# ProProject_8__2024-05-28.net
KiCad netlist of a schematic drawn in EasyEDA Pro
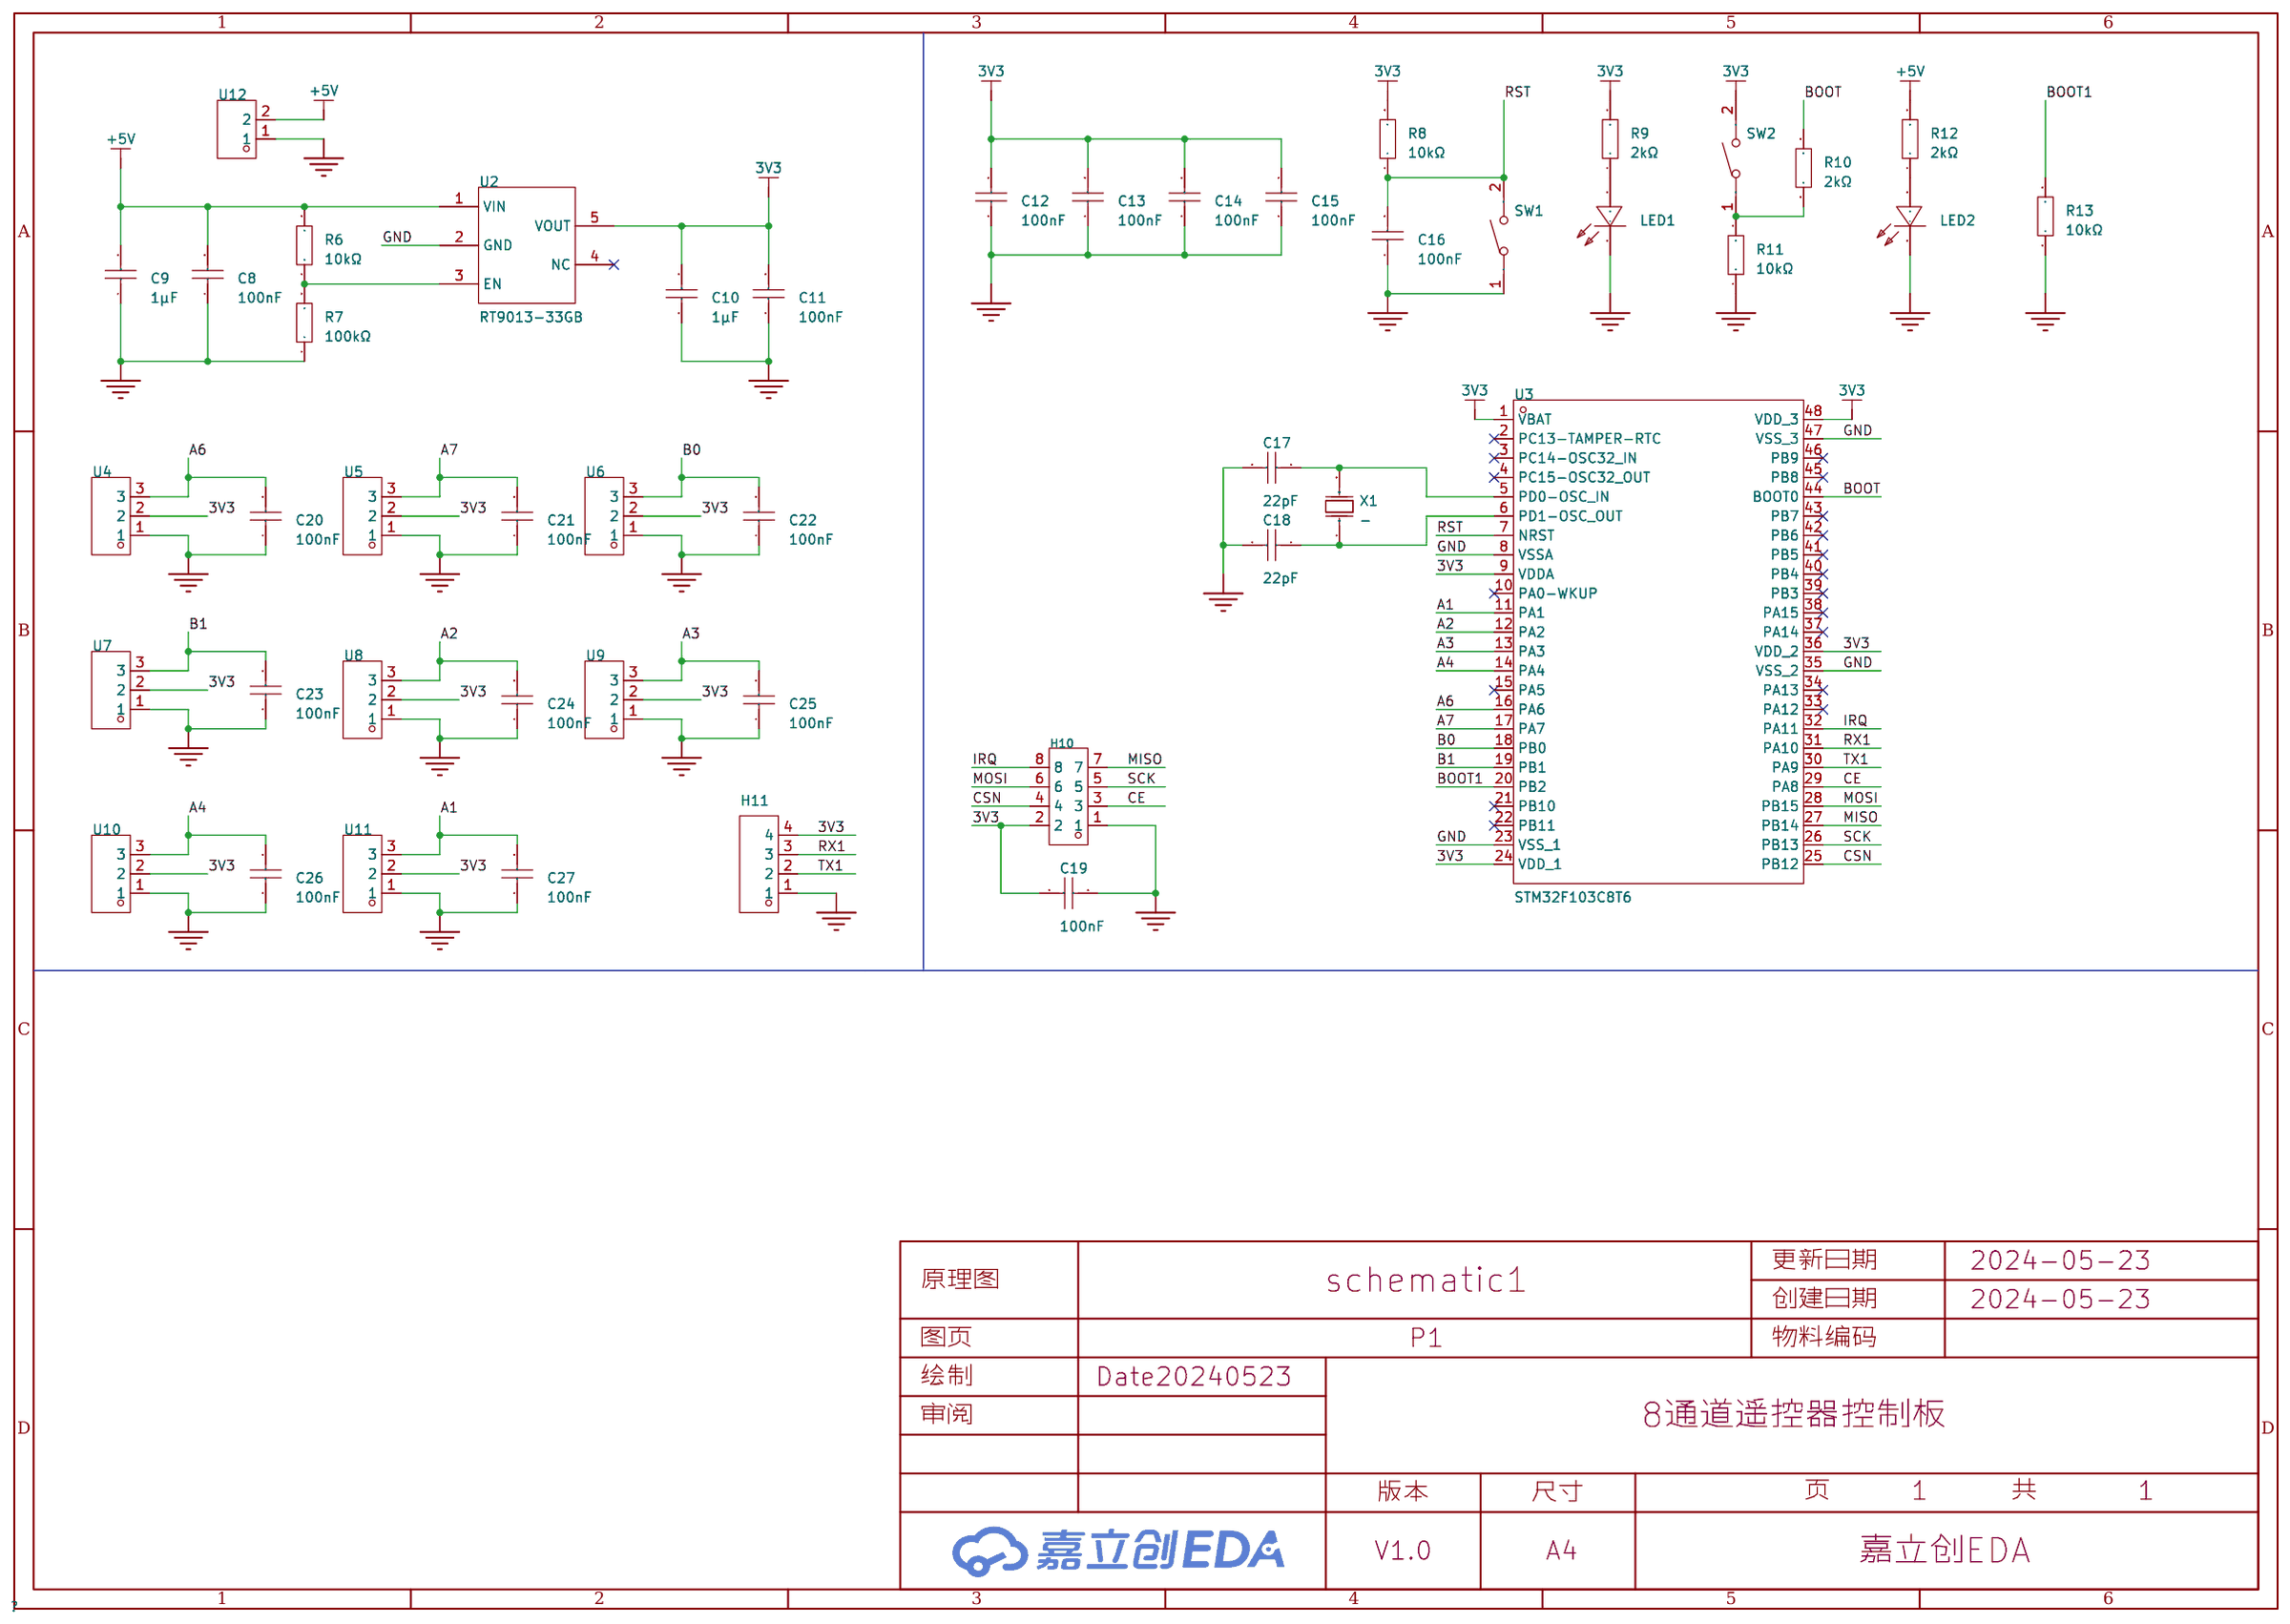
[diagram p0: schematic sheet]

(export (version "E")
  (design (tool "Eeschema 10.0.6"))
  (components
    (comp (ref "C8")
      (value "100nF")
      (footprint "easyedapro:C0805")
      (description "容值:100nF;精度:±10%;额定电压:50V;材质(温度系数):X7R;")
      (fields
        (field (name "Manufacturer Part") "CC0805KRX7R9BB104")
        (field (name "Manufacturer") "YAGEO(国巨)")
      )
      (libsource (lib "easyedapro") (part "CC0805KRX7R9BB104"))
    )
    (comp (ref "C9")
      (value "1μF")
      (footprint "easyedapro:C0805")
      (description "容值:100nF;精度:±10%;额定电压:50V;材质(温度系数):X7R;")
      (fields
        (field (name "Manufacturer Part") "CC0805KRX7R9BB104")
        (field (name "Manufacturer") "YAGEO(国巨)")
      )
      (libsource (lib "easyedapro") (part "CC0805KRX7R9BB104"))
    )
    (comp (ref "C10")
      (value "1μF")
      (footprint "easyedapro:C0805")
      (description "容值:100nF;精度:±10%;额定电压:50V;材质(温度系数):X7R;")
      (fields
        (field (name "Manufacturer Part") "CC0805KRX7R9BB104")
        (field (name "Manufacturer") "YAGEO(国巨)")
      )
      (libsource (lib "easyedapro") (part "CC0805KRX7R9BB104"))
    )
    (comp (ref "C11")
      (value "100nF")
      (footprint "easyedapro:C0805")
      (description "容值:100nF;精度:±10%;额定电压:50V;材质(温度系数):X7R;")
      (fields
        (field (name "Manufacturer Part") "CC0805KRX7R9BB104")
        (field (name "Manufacturer") "YAGEO(国巨)")
      )
      (libsource (lib "easyedapro") (part "CC0805KRX7R9BB104"))
    )
    (comp (ref "C12")
      (value "100nF")
      (footprint "easyedapro:C0805")
      (description "容值:100nF;精度:±10%;额定电压:50V;材质(温度系数):X7R;")
      (fields
        (field (name "Manufacturer Part") "CC0805KRX7R9BB104")
        (field (name "Manufacturer") "YAGEO(国巨)")
      )
      (libsource (lib "easyedapro") (part "CC0805KRX7R9BB104"))
    )
    (comp (ref "C13")
      (value "100nF")
      (footprint "easyedapro:C0805")
      (description "容值:100nF;精度:±10%;额定电压:50V;材质(温度系数):X7R;")
      (fields
        (field (name "Manufacturer Part") "CC0805KRX7R9BB104")
        (field (name "Manufacturer") "YAGEO(国巨)")
      )
      (libsource (lib "easyedapro") (part "CC0805KRX7R9BB104"))
    )
    (comp (ref "C14")
      (value "100nF")
      (footprint "easyedapro:C0805")
      (description "容值:100nF;精度:±10%;额定电压:50V;材质(温度系数):X7R;")
      (fields
        (field (name "Manufacturer Part") "CC0805KRX7R9BB104")
        (field (name "Manufacturer") "YAGEO(国巨)")
      )
      (libsource (lib "easyedapro") (part "CC0805KRX7R9BB104"))
    )
    (comp (ref "C15")
      (value "100nF")
      (footprint "easyedapro:C0805")
      (description "容值:100nF;精度:±10%;额定电压:50V;材质(温度系数):X7R;")
      (fields
        (field (name "Manufacturer Part") "CC0805KRX7R9BB104")
        (field (name "Manufacturer") "YAGEO(国巨)")
      )
      (libsource (lib "easyedapro") (part "CC0805KRX7R9BB104"))
    )
    (comp (ref "C16")
      (value "100nF")
      (footprint "easyedapro:C0805")
      (description "容值:100nF;精度:±10%;额定电压:50V;材质(温度系数):X7R;")
      (fields
        (field (name "Manufacturer Part") "CC0805KRX7R9BB104")
        (field (name "Manufacturer") "YAGEO(国巨)")
      )
      (libsource (lib "easyedapro") (part "CC0805KRX7R9BB104"))
    )
    (comp (ref "C17")
      (value "22pF")
      (footprint "easyedapro:C0805")
      (description "容值:100nF;精度:±10%;额定电压:50V;材质(温度系数):X7R;")
      (fields
        (field (name "Manufacturer Part") "CC0805KRX7R9BB104")
        (field (name "Manufacturer") "YAGEO(国巨)")
      )
      (libsource (lib "easyedapro") (part "CC0805KRX7R9BB104"))
    )
    (comp (ref "C18")
      (value "22pF")
      (footprint "easyedapro:C0805")
      (description "容值:100nF;精度:±10%;额定电压:50V;材质(温度系数):X7R;")
      (fields
        (field (name "Manufacturer Part") "CC0805KRX7R9BB104")
        (field (name "Manufacturer") "YAGEO(国巨)")
      )
      (libsource (lib "easyedapro") (part "CC0805KRX7R9BB104"))
    )
    (comp (ref "C19")
      (value "100nF")
      (footprint "easyedapro:C0805")
      (description "容值:100nF;精度:±10%;额定电压:50V;材质(温度系数):X7R;")
      (fields
        (field (name "Manufacturer Part") "CC0805KRX7R9BB104")
        (field (name "Manufacturer") "YAGEO(国巨)")
      )
      (libsource (lib "easyedapro") (part "CC0805KRX7R9BB104"))
    )
    (comp (ref "C20")
      (value "100nF")
      (footprint "easyedapro:C0805")
      (description "容值:100nF;精度:±10%;额定电压:50V;材质(温度系数):X7R;")
      (fields
        (field (name "Manufacturer Part") "CC0805KRX7R9BB104")
        (field (name "Manufacturer") "YAGEO(国巨)")
      )
      (libsource (lib "easyedapro") (part "CC0805KRX7R9BB104"))
    )
    (comp (ref "C21")
      (value "100nF")
      (footprint "easyedapro:C0805")
      (description "容值:100nF;精度:±10%;额定电压:50V;材质(温度系数):X7R;")
      (fields
        (field (name "Manufacturer Part") "CC0805KRX7R9BB104")
        (field (name "Manufacturer") "YAGEO(国巨)")
      )
      (libsource (lib "easyedapro") (part "CC0805KRX7R9BB104"))
    )
    (comp (ref "C22")
      (value "100nF")
      (footprint "easyedapro:C0805")
      (description "容值:100nF;精度:±10%;额定电压:50V;材质(温度系数):X7R;")
      (fields
        (field (name "Manufacturer Part") "CC0805KRX7R9BB104")
        (field (name "Manufacturer") "YAGEO(国巨)")
      )
      (libsource (lib "easyedapro") (part "CC0805KRX7R9BB104"))
    )
    (comp (ref "C23")
      (value "100nF")
      (footprint "easyedapro:C0805")
      (description "容值:100nF;精度:±10%;额定电压:50V;材质(温度系数):X7R;")
      (fields
        (field (name "Manufacturer Part") "CC0805KRX7R9BB104")
        (field (name "Manufacturer") "YAGEO(国巨)")
      )
      (libsource (lib "easyedapro") (part "CC0805KRX7R9BB104"))
    )
    (comp (ref "C24")
      (value "100nF")
      (footprint "easyedapro:C0805")
      (description "容值:100nF;精度:±10%;额定电压:50V;材质(温度系数):X7R;")
      (fields
        (field (name "Manufacturer Part") "CC0805KRX7R9BB104")
        (field (name "Manufacturer") "YAGEO(国巨)")
      )
      (libsource (lib "easyedapro") (part "CC0805KRX7R9BB104"))
    )
    (comp (ref "C25")
      (value "100nF")
      (footprint "easyedapro:C0805")
      (description "容值:100nF;精度:±10%;额定电压:50V;材质(温度系数):X7R;")
      (fields
        (field (name "Manufacturer Part") "CC0805KRX7R9BB104")
        (field (name "Manufacturer") "YAGEO(国巨)")
      )
      (libsource (lib "easyedapro") (part "CC0805KRX7R9BB104"))
    )
    (comp (ref "C26")
      (value "100nF")
      (footprint "easyedapro:C0805")
      (description "容值:100nF;精度:±10%;额定电压:50V;材质(温度系数):X7R;")
      (fields
        (field (name "Manufacturer Part") "CC0805KRX7R9BB104")
        (field (name "Manufacturer") "YAGEO(国巨)")
      )
      (libsource (lib "easyedapro") (part "CC0805KRX7R9BB104"))
    )
    (comp (ref "C27")
      (value "100nF")
      (footprint "easyedapro:C0805")
      (description "容值:100nF;精度:±10%;额定电压:50V;材质(温度系数):X7R;")
      (fields
        (field (name "Manufacturer Part") "CC0805KRX7R9BB104")
        (field (name "Manufacturer") "YAGEO(国巨)")
      )
      (libsource (lib "easyedapro") (part "CC0805KRX7R9BB104"))
    )
    (comp (ref "H10")
      (value "PZ254V-12-8P")
      (footprint "easyedapro:HDR-TH_8P-P2.54-V-M-R2-C4-S2.54")
      (fields (field (name "Manufacturer") "XFCN(兴飞)"))
      (libsource (lib "easyedapro") (part "PZ254V-12-8P"))
    )
    (comp (ref "H11")
      (value "PZ254V-11-04P")
      (footprint "easyedapro:HDR-TH_4P-P2.54-V-M")
      (fields (field (name "Manufacturer") "XFCN(兴飞)"))
      (libsource (lib "easyedapro") (part "PZ254V-11-04P_C2691448"))
    )
    (comp (ref "LED1")
      (value "SZYY0603G")
      (footprint "easyedapro:LED0603-R-RD_GREEN")
      (description "发光颜色:翠绿色;")
      (fields (field (name "Manufacturer") "yongyu(永裕光电)"))
      (libsource (lib "easyedapro") (part "SZYY0603G"))
    )
    (comp (ref "LED2")
      (value "SZYY0603G")
      (footprint "easyedapro:LED0603-R-RD_GREEN")
      (description "发光颜色:翠绿色;")
      (fields (field (name "Manufacturer") "yongyu(永裕光电)"))
      (libsource (lib "easyedapro") (part "SZYY0603G"))
    )
    (comp (ref "R6")
      (value "10kΩ")
      (footprint "easyedapro:R0603")
      (description "电阻类型:厚膜电阻;阻值:1kΩ;精度:±1%;功率:100mW;最大工作电压:75V;温度系数:±100ppm/°C;")
      (fields
        (field (name "Manufacturer Part") "0603WAF1001T5E")
        (field (name "Manufacturer") "UNI-ROYAL(厚声)")
      )
      (libsource (lib "easyedapro") (part "0603WAF1001T5E"))
    )
    (comp (ref "R7")
      (value "100kΩ")
      (footprint "easyedapro:R0603")
      (description "电阻类型:厚膜电阻;阻值:1kΩ;精度:±1%;功率:100mW;最大工作电压:75V;温度系数:±100ppm/°C;")
      (fields
        (field (name "Manufacturer Part") "0603WAF1001T5E")
        (field (name "Manufacturer") "UNI-ROYAL(厚声)")
      )
      (libsource (lib "easyedapro") (part "0603WAF1001T5E"))
    )
    (comp (ref "R8")
      (value "10kΩ")
      (footprint "easyedapro:R0603")
      (description "电阻类型:厚膜电阻;阻值:1kΩ;精度:±1%;功率:100mW;最大工作电压:75V;温度系数:±100ppm/°C;")
      (fields
        (field (name "Manufacturer Part") "0603WAF1001T5E")
        (field (name "Manufacturer") "UNI-ROYAL(厚声)")
      )
      (libsource (lib "easyedapro") (part "0603WAF1001T5E"))
    )
    (comp (ref "R9")
      (value "2kΩ")
      (footprint "easyedapro:R0603")
      (description "电阻类型:厚膜电阻;阻值:1kΩ;精度:±1%;功率:100mW;最大工作电压:75V;温度系数:±100ppm/°C;")
      (fields
        (field (name "Manufacturer Part") "0603WAF1001T5E")
        (field (name "Manufacturer") "UNI-ROYAL(厚声)")
      )
      (libsource (lib "easyedapro") (part "0603WAF1001T5E"))
    )
    (comp (ref "R10")
      (value "2kΩ")
      (footprint "easyedapro:R0603")
      (description "电阻类型:厚膜电阻;阻值:1kΩ;精度:±1%;功率:100mW;最大工作电压:75V;温度系数:±100ppm/°C;")
      (fields
        (field (name "Manufacturer Part") "0603WAF1001T5E")
        (field (name "Manufacturer") "UNI-ROYAL(厚声)")
      )
      (libsource (lib "easyedapro") (part "0603WAF1001T5E"))
    )
    (comp (ref "R11")
      (value "10kΩ")
      (footprint "easyedapro:R0603")
      (description "电阻类型:厚膜电阻;阻值:1kΩ;精度:±1%;功率:100mW;最大工作电压:75V;温度系数:±100ppm/°C;")
      (fields
        (field (name "Manufacturer Part") "0603WAF1001T5E")
        (field (name "Manufacturer") "UNI-ROYAL(厚声)")
      )
      (libsource (lib "easyedapro") (part "0603WAF1001T5E"))
    )
    (comp (ref "R12")
      (value "2kΩ")
      (footprint "easyedapro:R0603")
      (description "电阻类型:厚膜电阻;阻值:1kΩ;精度:±1%;功率:100mW;最大工作电压:75V;温度系数:±100ppm/°C;")
      (fields
        (field (name "Manufacturer Part") "0603WAF1001T5E")
        (field (name "Manufacturer") "UNI-ROYAL(厚声)")
      )
      (libsource (lib "easyedapro") (part "0603WAF1001T5E"))
    )
    (comp (ref "R13")
      (value "10kΩ")
      (footprint "easyedapro:R0603")
      (description "电阻类型:厚膜电阻;阻值:1kΩ;精度:±1%;功率:100mW;最大工作电压:75V;温度系数:±100ppm/°C;")
      (fields
        (field (name "Manufacturer Part") "0603WAF1001T5E")
        (field (name "Manufacturer") "UNI-ROYAL(厚声)")
      )
      (libsource (lib "easyedapro") (part "0603WAF1001T5E"))
    )
    (comp (ref "SW1")
      (value "TS-1088-AR02016")
      (footprint "easyedapro:SW-SMD_L3.9-W3.0-P4.45")
      (fields (field (name "Manufacturer") "XUNPU(讯普)"))
      (libsource (lib "easyedapro") (part "TS-1088-AR02016"))
    )
    (comp (ref "SW2")
      (value "TS-1088-AR02016")
      (footprint "easyedapro:SW-SMD_L3.9-W3.0-P4.45")
      (fields (field (name "Manufacturer") "XUNPU(讯普)"))
      (libsource (lib "easyedapro") (part "TS-1088-AR02016"))
    )
    (comp (ref "U2")
      (value "RT9013-33GB")
      (footprint "easyedapro:SOT-23-5_L3.0-W1.7-P0.95-LS2.8-BL")
      (description "输出类型:固定;最大输入电压:5.5V;输出电压:3.3V;最大输出电流:500mA;电源纹波抑制比(PSRR):50dB@(10kHz);输出极性:正极;")
      (fields (field (name "Manufacturer") "RICHTEK(立锜)"))
      (libsource (lib "easyedapro") (part "RT9013-33GB"))
    )
    (comp (ref "U3")
      (value "STM32F103C8T6")
      (footprint "easyedapro:LQFP-48_L7.0-W7.0-P0.50-LS9.0-BL")
      (description "CPU内核:CM3;程序存储容量:64KB;RAM总容量:20KB;GPIO端口数量:37;工作电压范围:2V~3.6V;CPU最大主频:72MHz;程序存储器类型:FLASH;")
      (fields (field (name "Manufacturer") "ST(意法半导体)"))
      (libsource (lib "easyedapro") (part "STM32F103C8T6"))
    )
    (comp (ref "U4")
      (value "ZX-XH2.54-3PZZ")
      (footprint "easyedapro:CONN-TH_3P-P2.54_2501S-3P")
      (fields (field (name "Manufacturer") "Megastar(兆星)"))
      (libsource (lib "easyedapro") (part "ZX-XH2.54-3PZZ"))
    )
    (comp (ref "U5")
      (value "ZX-XH2.54-3PZZ")
      (footprint "easyedapro:CONN-TH_3P-P2.54_2501S-3P")
      (fields (field (name "Manufacturer") "Megastar(兆星)"))
      (libsource (lib "easyedapro") (part "ZX-XH2.54-3PZZ"))
    )
    (comp (ref "U6")
      (value "ZX-XH2.54-3PZZ")
      (footprint "easyedapro:CONN-TH_3P-P2.54_2501S-3P")
      (fields (field (name "Manufacturer") "Megastar(兆星)"))
      (libsource (lib "easyedapro") (part "ZX-XH2.54-3PZZ"))
    )
    (comp (ref "U7")
      (value "ZX-XH2.54-3PZZ")
      (footprint "easyedapro:CONN-TH_3P-P2.54_2501S-3P")
      (fields (field (name "Manufacturer") "Megastar(兆星)"))
      (libsource (lib "easyedapro") (part "ZX-XH2.54-3PZZ"))
    )
    (comp (ref "U8")
      (value "ZX-XH2.54-3PZZ")
      (footprint "easyedapro:CONN-TH_3P-P2.54_2501S-3P")
      (fields (field (name "Manufacturer") "Megastar(兆星)"))
      (libsource (lib "easyedapro") (part "ZX-XH2.54-3PZZ"))
    )
    (comp (ref "U9")
      (value "ZX-XH2.54-3PZZ")
      (footprint "easyedapro:CONN-TH_3P-P2.54_2501S-3P")
      (fields (field (name "Manufacturer") "Megastar(兆星)"))
      (libsource (lib "easyedapro") (part "ZX-XH2.54-3PZZ"))
    )
    (comp (ref "U10")
      (value "ZX-XH2.54-3PZZ")
      (footprint "easyedapro:CONN-TH_3P-P2.54_2501S-3P")
      (fields (field (name "Manufacturer") "Megastar(兆星)"))
      (libsource (lib "easyedapro") (part "ZX-XH2.54-3PZZ"))
    )
    (comp (ref "U11")
      (value "ZX-XH2.54-3PZZ")
      (footprint "easyedapro:CONN-TH_3P-P2.54_2501S-3P")
      (fields (field (name "Manufacturer") "Megastar(兆星)"))
      (libsource (lib "easyedapro") (part "ZX-XH2.54-3PZZ"))
    )
    (comp (ref "U12")
      (value "DB125-3.81-2P-GN-S")
      (footprint "easyedapro:CONN-TH_2P-P3.81_L7.4-W7.6")
      (fields (field (name "Manufacturer") "DORABO(地博电气)"))
      (libsource (lib "easyedapro") (part "DB125-3.81-2P"))
    )
    (comp (ref "X1")
      (value "-")
      (footprint "easyedapro:HC-49S_L11.4-W4.8")
      (description "晶振类型:-;频率:-;外接负载电容:-;")
      (fields (field (name "Manufacturer Part") "9C08000003") (field (name "Manufacturer") "TXC(晶技)"))
      (libsource (lib "easyedapro") (part "9C0803LCSC-DDK2S"))
    )
  )
  (nets
    (net (code "1") (name "+5V") (class "Default")
      (node (ref "C8") (pin "2") (pinfunction "2_2") (pintype "input"))
      (node (ref "C9") (pin "2") (pinfunction "2_2") (pintype "input"))
      (node (ref "R12") (pin "2") (pinfunction "2_2") (pintype "input"))
      (node (ref "R6") (pin "2") (pinfunction "2_2") (pintype "input"))
      (node (ref "U12") (pin "2") (pinfunction "2_2") (pintype "unspecified"))
      (node (ref "U2") (pin "1") (pinfunction "VIN_1") (pintype "unspecified"))
    )
    (net (code "2") (name "/A1") (class "Default")
      (node (ref "C27") (pin "2") (pinfunction "2_2") (pintype "input"))
      (node (ref "U11") (pin "3") (pinfunction "3_3") (pintype "unspecified"))
      (node (ref "U3") (pin "11") (pinfunction "PA1_11") (pintype "unspecified"))
    )
    (net (code "3") (name "/A2") (class "Default")
      (node (ref "C24") (pin "2") (pinfunction "2_2") (pintype "input"))
      (node (ref "U3") (pin "12") (pinfunction "PA2_12") (pintype "unspecified"))
      (node (ref "U8") (pin "3") (pinfunction "3_3") (pintype "unspecified"))
    )
    (net (code "4") (name "/A3") (class "Default")
      (node (ref "C25") (pin "2") (pinfunction "2_2") (pintype "input"))
      (node (ref "U3") (pin "13") (pinfunction "PA3_13") (pintype "unspecified"))
      (node (ref "U9") (pin "3") (pinfunction "3_3") (pintype "unspecified"))
    )
    (net (code "5") (name "/A4") (class "Default")
      (node (ref "C26") (pin "2") (pinfunction "2_2") (pintype "input"))
      (node (ref "U10") (pin "3") (pinfunction "3_3") (pintype "unspecified"))
      (node (ref "U3") (pin "14") (pinfunction "PA4_14") (pintype "unspecified"))
    )
    (net (code "6") (name "/A6") (class "Default")
      (node (ref "C20") (pin "2") (pinfunction "2_2") (pintype "input"))
      (node (ref "U3") (pin "16") (pinfunction "PA6_16") (pintype "unspecified"))
      (node (ref "U4") (pin "3") (pinfunction "3_3") (pintype "unspecified"))
    )
    (net (code "7") (name "/A7") (class "Default")
      (node (ref "C21") (pin "2") (pinfunction "2_2") (pintype "input"))
      (node (ref "U3") (pin "17") (pinfunction "PA7_17") (pintype "unspecified"))
      (node (ref "U5") (pin "3") (pinfunction "3_3") (pintype "unspecified"))
    )
    (net (code "8") (name "/B0") (class "Default")
      (node (ref "C22") (pin "2") (pinfunction "2_2") (pintype "input"))
      (node (ref "U3") (pin "18") (pinfunction "PB0_18") (pintype "unspecified"))
      (node (ref "U6") (pin "3") (pinfunction "3_3") (pintype "unspecified"))
    )
    (net (code "9") (name "/B1") (class "Default")
      (node (ref "C23") (pin "2") (pinfunction "2_2") (pintype "input"))
      (node (ref "U3") (pin "19") (pinfunction "PB1_19") (pintype "unspecified"))
      (node (ref "U7") (pin "3") (pinfunction "3_3") (pintype "unspecified"))
    )
    (net (code "10") (name "/BOOT") (class "Default")
      (node (ref "R10") (pin "2") (pinfunction "2_2") (pintype "input"))
      (node (ref "U3") (pin "44") (pinfunction "BOOT0_44") (pintype "unspecified"))
    )
    (net (code "11") (name "/BOOT1") (class "Default")
      (node (ref "R13") (pin "2") (pinfunction "2_2") (pintype "input"))
      (node (ref "U3") (pin "20") (pinfunction "PB2_20") (pintype "unspecified"))
    )
    (net (code "12") (name "/CE") (class "Default")
      (node (ref "H10") (pin "3") (pinfunction "3_3") (pintype "input"))
      (node (ref "U3") (pin "29") (pinfunction "PA8_29") (pintype "unspecified"))
    )
    (net (code "13") (name "/CSN") (class "Default")
      (node (ref "H10") (pin "4") (pinfunction "4_4") (pintype "input"))
      (node (ref "U3") (pin "25") (pinfunction "PB12_25") (pintype "unspecified"))
    )
    (net (code "14") (name "/IRQ") (class "Default")
      (node (ref "H10") (pin "8") (pinfunction "8_8") (pintype "input"))
      (node (ref "U3") (pin "32") (pinfunction "PA11_32") (pintype "unspecified"))
    )
    (net (code "15") (name "/MISO") (class "Default")
      (node (ref "H10") (pin "7") (pinfunction "7_7") (pintype "input"))
      (node (ref "U3") (pin "27") (pinfunction "PB14_27") (pintype "unspecified"))
    )
    (net (code "16") (name "/MOSI") (class "Default")
      (node (ref "H10") (pin "6") (pinfunction "6_6") (pintype "input"))
      (node (ref "U3") (pin "28") (pinfunction "PB15_28") (pintype "unspecified"))
    )
    (net (code "17") (name "/RST") (class "Default")
      (node (ref "C16") (pin "2") (pinfunction "2_2") (pintype "input"))
      (node (ref "R8") (pin "1") (pinfunction "1_1") (pintype "input"))
      (node (ref "SW1") (pin "2") (pinfunction "2_2") (pintype "unspecified"))
      (node (ref "U3") (pin "7") (pinfunction "NRST_7") (pintype "unspecified"))
    )
    (net (code "18") (name "/RX1") (class "Default")
      (node (ref "H11") (pin "3") (pinfunction "3_3") (pintype "unspecified"))
      (node (ref "U3") (pin "31") (pinfunction "PA10_31") (pintype "unspecified"))
    )
    (net (code "19") (name "/SCK") (class "Default")
      (node (ref "H10") (pin "5") (pinfunction "5_5") (pintype "input"))
      (node (ref "U3") (pin "26") (pinfunction "PB13_26") (pintype "unspecified"))
    )
    (net (code "20") (name "/TX1") (class "Default")
      (node (ref "H11") (pin "2") (pinfunction "2_2") (pintype "unspecified"))
      (node (ref "U3") (pin "30") (pinfunction "PA9_30") (pintype "unspecified"))
    )
    (net (code "21") (name "3V3") (class "Default")
      (node (ref "C10") (pin "2") (pinfunction "2_2") (pintype "input"))
      (node (ref "C11") (pin "2") (pinfunction "2_2") (pintype "input"))
      (node (ref "C12") (pin "2") (pinfunction "2_2") (pintype "input"))
      (node (ref "C13") (pin "2") (pinfunction "2_2") (pintype "input"))
      (node (ref "C14") (pin "2") (pinfunction "2_2") (pintype "input"))
      (node (ref "C15") (pin "2") (pinfunction "2_2") (pintype "input"))
      (node (ref "C19") (pin "1") (pinfunction "1_1") (pintype "input"))
      (node (ref "H10") (pin "2") (pinfunction "2_2") (pintype "input"))
      (node (ref "H11") (pin "4") (pinfunction "4_4") (pintype "unspecified"))
      (node (ref "R8") (pin "2") (pinfunction "2_2") (pintype "input"))
      (node (ref "R9") (pin "2") (pinfunction "2_2") (pintype "input"))
      (node (ref "SW2") (pin "2") (pinfunction "2_2") (pintype "unspecified"))
      (node (ref "U10") (pin "2") (pinfunction "2_2") (pintype "unspecified"))
      (node (ref "U11") (pin "2") (pinfunction "2_2") (pintype "unspecified"))
      (node (ref "U2") (pin "5") (pinfunction "VOUT_5") (pintype "unspecified"))
      (node (ref "U3") (pin "1") (pinfunction "VBAT_1") (pintype "unspecified"))
      (node (ref "U3") (pin "24") (pinfunction "VDD_1_24") (pintype "unspecified"))
      (node (ref "U3") (pin "36") (pinfunction "VDD_2_36") (pintype "unspecified"))
      (node (ref "U3") (pin "48") (pinfunction "VDD_3_48") (pintype "unspecified"))
      (node (ref "U3") (pin "9") (pinfunction "VDDA_9") (pintype "unspecified"))
      (node (ref "U4") (pin "2") (pinfunction "2_2") (pintype "unspecified"))
      (node (ref "U5") (pin "2") (pinfunction "2_2") (pintype "unspecified"))
      (node (ref "U6") (pin "2") (pinfunction "2_2") (pintype "unspecified"))
      (node (ref "U7") (pin "2") (pinfunction "2_2") (pintype "unspecified"))
      (node (ref "U8") (pin "2") (pinfunction "2_2") (pintype "unspecified"))
      (node (ref "U9") (pin "2") (pinfunction "2_2") (pintype "unspecified"))
    )
    (net (code "22") (name "GND") (class "Default")
      (node (ref "C10") (pin "1") (pinfunction "1_1") (pintype "input"))
      (node (ref "C11") (pin "1") (pinfunction "1_1") (pintype "input"))
      (node (ref "C12") (pin "1") (pinfunction "1_1") (pintype "input"))
      (node (ref "C13") (pin "1") (pinfunction "1_1") (pintype "input"))
      (node (ref "C14") (pin "1") (pinfunction "1_1") (pintype "input"))
      (node (ref "C15") (pin "1") (pinfunction "1_1") (pintype "input"))
      (node (ref "C16") (pin "1") (pinfunction "1_1") (pintype "input"))
      (node (ref "C17") (pin "2") (pinfunction "2_2") (pintype "input"))
      (node (ref "C18") (pin "2") (pinfunction "2_2") (pintype "input"))
      (node (ref "C19") (pin "2") (pinfunction "2_2") (pintype "input"))
      (node (ref "C20") (pin "1") (pinfunction "1_1") (pintype "input"))
      (node (ref "C21") (pin "1") (pinfunction "1_1") (pintype "input"))
      (node (ref "C22") (pin "1") (pinfunction "1_1") (pintype "input"))
      (node (ref "C23") (pin "1") (pinfunction "1_1") (pintype "input"))
      (node (ref "C24") (pin "1") (pinfunction "1_1") (pintype "input"))
      (node (ref "C25") (pin "1") (pinfunction "1_1") (pintype "input"))
      (node (ref "C26") (pin "1") (pinfunction "1_1") (pintype "input"))
      (node (ref "C27") (pin "1") (pinfunction "1_1") (pintype "input"))
      (node (ref "C8") (pin "1") (pinfunction "1_1") (pintype "input"))
      (node (ref "C9") (pin "1") (pinfunction "1_1") (pintype "input"))
      (node (ref "H10") (pin "1") (pinfunction "1_1") (pintype "input"))
      (node (ref "H11") (pin "1") (pinfunction "1_1") (pintype "unspecified"))
      (node (ref "LED1") (pin "2") (pinfunction "-_2") (pintype "unspecified"))
      (node (ref "LED2") (pin "2") (pinfunction "-_2") (pintype "unspecified"))
      (node (ref "R11") (pin "1") (pinfunction "1_1") (pintype "input"))
      (node (ref "R13") (pin "1") (pinfunction "1_1") (pintype "input"))
      (node (ref "R7") (pin "1") (pinfunction "1_1") (pintype "input"))
      (node (ref "SW1") (pin "1") (pinfunction "1_1") (pintype "unspecified"))
      (node (ref "U10") (pin "1") (pinfunction "1_1") (pintype "unspecified"))
      (node (ref "U11") (pin "1") (pinfunction "1_1") (pintype "unspecified"))
      (node (ref "U12") (pin "1") (pinfunction "1_1") (pintype "unspecified"))
      (node (ref "U2") (pin "2") (pinfunction "GND_2") (pintype "unspecified"))
      (node (ref "U3") (pin "23") (pinfunction "VSS_1_23") (pintype "unspecified"))
      (node (ref "U3") (pin "35") (pinfunction "VSS_2_35") (pintype "unspecified"))
      (node (ref "U3") (pin "47") (pinfunction "VSS_3_47") (pintype "unspecified"))
      (node (ref "U3") (pin "8") (pinfunction "VSSA_8") (pintype "unspecified"))
      (node (ref "U4") (pin "1") (pinfunction "1_1") (pintype "unspecified"))
      (node (ref "U5") (pin "1") (pinfunction "1_1") (pintype "unspecified"))
      (node (ref "U6") (pin "1") (pinfunction "1_1") (pintype "unspecified"))
      (node (ref "U7") (pin "1") (pinfunction "1_1") (pintype "unspecified"))
      (node (ref "U8") (pin "1") (pinfunction "1_1") (pintype "unspecified"))
      (node (ref "U9") (pin "1") (pinfunction "1_1") (pintype "unspecified"))
    )
    (net (code "23") (name "Net-(LED1-+)") (class "Default")
      (node (ref "LED1") (pin "1") (pinfunction "+_1") (pintype "unspecified"))
      (node (ref "R9") (pin "1") (pinfunction "1_1") (pintype "input"))
    )
    (net (code "24") (name "Net-(LED2-+)") (class "Default")
      (node (ref "LED2") (pin "1") (pinfunction "+_1") (pintype "unspecified"))
      (node (ref "R12") (pin "1") (pinfunction "1_1") (pintype "input"))
    )
    (net (code "25") (name "Net-(R10-Pad1)") (class "Default")
      (node (ref "R10") (pin "1") (pinfunction "1_1") (pintype "input"))
      (node (ref "R11") (pin "2") (pinfunction "2_2") (pintype "input"))
      (node (ref "SW2") (pin "1") (pinfunction "1_1") (pintype "unspecified"))
    )
    (net (code "26") (name "Net-(U2-EN)") (class "Default")
      (node (ref "R6") (pin "1") (pinfunction "1_1") (pintype "input"))
      (node (ref "R7") (pin "2") (pinfunction "2_2") (pintype "input"))
      (node (ref "U2") (pin "3") (pinfunction "EN_3") (pintype "unspecified"))
    )
    (net (code "27") (name "Net-(U3-PD0-OSC_IN)") (class "Default")
      (node (ref "C17") (pin "1") (pinfunction "1_1") (pintype "input"))
      (node (ref "U3") (pin "5") (pinfunction "PD0-OSC_IN_5") (pintype "unspecified"))
      (node (ref "X1") (pin "2") (pinfunction "OSC2_2") (pintype "input"))
    )
    (net (code "28") (name "Net-(U3-PD1-OSC_OUT)") (class "Default")
      (node (ref "C18") (pin "1") (pinfunction "1_1") (pintype "input"))
      (node (ref "U3") (pin "6") (pinfunction "PD1-OSC_OUT_6") (pintype "unspecified"))
      (node (ref "X1") (pin "1") (pinfunction "OSC1_1") (pintype "input"))
    )
    (net (code "29") (name "unconnected-(U2-NC-Pad4)") (class "Default")
      (node (ref "U2") (pin "4") (pinfunction "NC_4") (pintype "unspecified+no_connect"))
    )
    (net (code "30") (name "unconnected-(U3-PA0-WKUP-Pad10)") (class "Default")
      (node (ref "U3") (pin "10") (pinfunction "PA0-WKUP_10") (pintype "unspecified+no_connect"))
    )
    (net (code "31") (name "unconnected-(U3-PA5-Pad15)") (class "Default")
      (node (ref "U3") (pin "15") (pinfunction "PA5_15") (pintype "unspecified+no_connect"))
    )
    (net (code "32") (name "unconnected-(U3-PA12-Pad33)") (class "Default")
      (node (ref "U3") (pin "33") (pinfunction "PA12_33") (pintype "unspecified+no_connect"))
    )
    (net (code "33") (name "unconnected-(U3-PA13-Pad34)") (class "Default")
      (node (ref "U3") (pin "34") (pinfunction "PA13_34") (pintype "unspecified+no_connect"))
    )
    (net (code "34") (name "unconnected-(U3-PA14-Pad37)") (class "Default")
      (node (ref "U3") (pin "37") (pinfunction "PA14_37") (pintype "unspecified+no_connect"))
    )
    (net (code "35") (name "unconnected-(U3-PA15-Pad38)") (class "Default")
      (node (ref "U3") (pin "38") (pinfunction "PA15_38") (pintype "unspecified+no_connect"))
    )
    (net (code "36") (name "unconnected-(U3-PB3-Pad39)") (class "Default")
      (node (ref "U3") (pin "39") (pinfunction "PB3_39") (pintype "unspecified+no_connect"))
    )
    (net (code "37") (name "unconnected-(U3-PB4-Pad40)") (class "Default")
      (node (ref "U3") (pin "40") (pinfunction "PB4_40") (pintype "unspecified+no_connect"))
    )
    (net (code "38") (name "unconnected-(U3-PB5-Pad41)") (class "Default")
      (node (ref "U3") (pin "41") (pinfunction "PB5_41") (pintype "unspecified+no_connect"))
    )
    (net (code "39") (name "unconnected-(U3-PB6-Pad42)") (class "Default")
      (node (ref "U3") (pin "42") (pinfunction "PB6_42") (pintype "unspecified+no_connect"))
    )
    (net (code "40") (name "unconnected-(U3-PB7-Pad43)") (class "Default")
      (node (ref "U3") (pin "43") (pinfunction "PB7_43") (pintype "unspecified+no_connect"))
    )
    (net (code "41") (name "unconnected-(U3-PB8-Pad45)") (class "Default")
      (node (ref "U3") (pin "45") (pinfunction "PB8_45") (pintype "unspecified+no_connect"))
    )
    (net (code "42") (name "unconnected-(U3-PB9-Pad46)") (class "Default")
      (node (ref "U3") (pin "46") (pinfunction "PB9_46") (pintype "unspecified+no_connect"))
    )
    (net (code "43") (name "unconnected-(U3-PB10-Pad21)") (class "Default")
      (node (ref "U3") (pin "21") (pinfunction "PB10_21") (pintype "unspecified+no_connect"))
    )
    (net (code "44") (name "unconnected-(U3-PB11-Pad22)") (class "Default")
      (node (ref "U3") (pin "22") (pinfunction "PB11_22") (pintype "unspecified+no_connect"))
    )
    (net (code "45") (name "unconnected-(U3-PC13-TAMPER-RTC-Pad2)") (class "Default")
      (node (ref "U3") (pin "2") (pinfunction "PC13-TAMPER-RTC_2") (pintype "unspecified+no_connect"))
    )
    (net (code "46") (name "unconnected-(U3-PC14-OSC32_IN-Pad3)") (class "Default")
      (node (ref "U3") (pin "3") (pinfunction "PC14-OSC32_IN_3") (pintype "unspecified+no_connect"))
    )
    (net (code "47") (name "unconnected-(U3-PC15-OSC32_OUT-Pad4)") (class "Default")
      (node (ref "U3") (pin "4") (pinfunction "PC15-OSC32_OUT_4") (pintype "unspecified+no_connect"))
    )
  )
)
